# FDC9266_floppy_korr.net
KiCad netlist of a schematic drawn in EAGLE
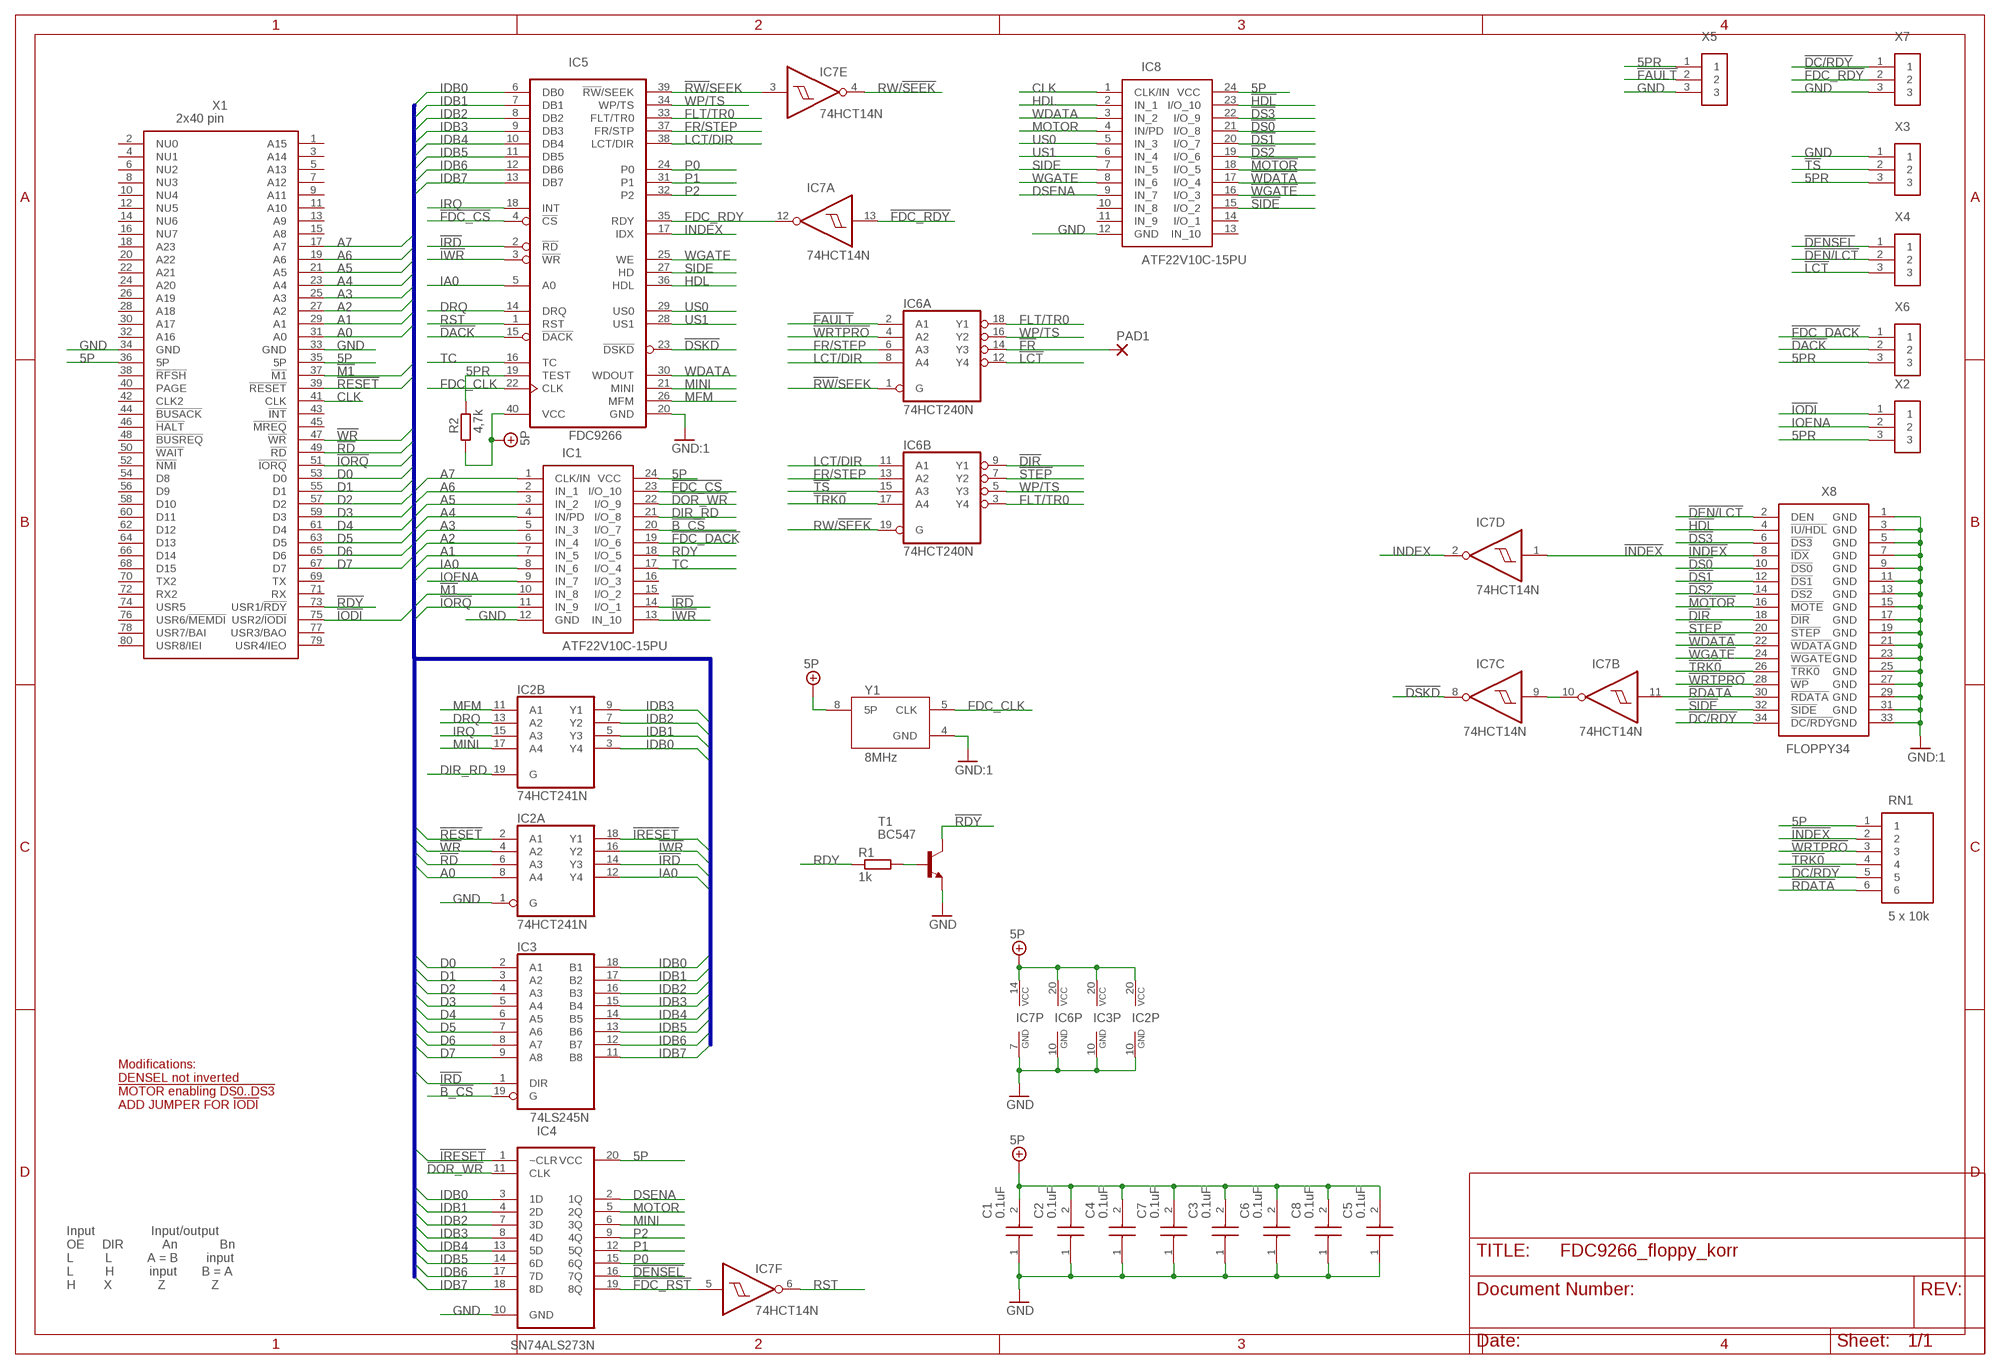
[diagram p0: schematic, sheet 1]

(export (version "E")
  (design (tool "Eeschema 10.0.6"))
  (components
    (comp (ref "C1")
      (value "0.1uF")
      (footprint "eagle-import:C315C103K5R5TA7303")
      (fields
        (field (name "ARROW_PART_NUMBER") "C315C103K5R5TA7303")
        (field (name "MOUSER_PART_NUMBER") "80-C315C103K5R-TR")
      )
      (libsource (lib "eagle-import") (part "C315C103K5R5TA7303"))
    )
    (comp (ref "C2")
      (value "0.1uF")
      (footprint "eagle-import:C315C103K5R5TA7303")
      (fields
        (field (name "ARROW_PART_NUMBER") "C315C103K5R5TA7303")
        (field (name "MOUSER_PART_NUMBER") "80-C315C103K5R-TR")
      )
      (libsource (lib "eagle-import") (part "C315C103K5R5TA7303"))
    )
    (comp (ref "C3")
      (value "0.1uF")
      (footprint "eagle-import:C315C103K5R5TA7303")
      (fields
        (field (name "ARROW_PART_NUMBER") "C315C103K5R5TA7303")
        (field (name "MOUSER_PART_NUMBER") "80-C315C103K5R-TR")
      )
      (libsource (lib "eagle-import") (part "C315C103K5R5TA7303"))
    )
    (comp (ref "C4")
      (value "0.1uF")
      (footprint "eagle-import:C315C103K5R5TA7303")
      (fields
        (field (name "ARROW_PART_NUMBER") "C315C103K5R5TA7303")
        (field (name "MOUSER_PART_NUMBER") "80-C315C103K5R-TR")
      )
      (libsource (lib "eagle-import") (part "C315C103K5R5TA7303"))
    )
    (comp (ref "C5")
      (value "0.1uF")
      (footprint "eagle-import:C315C103K5R5TA7303")
      (fields
        (field (name "ARROW_PART_NUMBER") "C315C103K5R5TA7303")
        (field (name "MOUSER_PART_NUMBER") "80-C315C103K5R-TR")
      )
      (libsource (lib "eagle-import") (part "C315C103K5R5TA7303"))
    )
    (comp (ref "C6")
      (value "0.1uF")
      (footprint "eagle-import:C315C103K5R5TA7303")
      (fields
        (field (name "ARROW_PART_NUMBER") "C315C103K5R5TA7303")
        (field (name "MOUSER_PART_NUMBER") "80-C315C103K5R-TR")
      )
      (libsource (lib "eagle-import") (part "C315C103K5R5TA7303"))
    )
    (comp (ref "C7")
      (value "0.1uF")
      (footprint "eagle-import:C315C103K5R5TA7303")
      (fields
        (field (name "ARROW_PART_NUMBER") "C315C103K5R5TA7303")
        (field (name "MOUSER_PART_NUMBER") "80-C315C103K5R-TR")
      )
      (libsource (lib "eagle-import") (part "C315C103K5R5TA7303"))
    )
    (comp (ref "C8")
      (value "0.1uF")
      (footprint "eagle-import:C315C103K5R5TA7303")
      (fields
        (field (name "ARROW_PART_NUMBER") "C315C103K5R5TA7303")
        (field (name "MOUSER_PART_NUMBER") "80-C315C103K5R-TR")
      )
      (libsource (lib "eagle-import") (part "C315C103K5R5TA7303"))
    )
    (comp (ref "IC1")
      (value "ATF22V10C-15PU")
      (footprint "eagle-import:DIP794W56P254L3188H533Q24N")
      (fields (field (name "MOUSER_PART_NUMBER") "556-AF22V10C15PU"))
      (libsource (lib "eagle-import") (part "ATF22V10C-15PU"))
    )
    (comp (ref "IC2")
      (value "74HCT241N")
      (footprint "eagle-import:DIL20")
      (libsource (lib "eagle-import") (part "74241NHCT"))
    )
    (comp (ref "IC3")
      (value "74LS245N")
      (footprint "eagle-import:DIL20")
      (libsource (lib "eagle-import") (part "74245NLS"))
    )
    (comp (ref "IC4")
      (value "SN74ALS273N")
      (footprint "eagle-import:DIP254P762X508-20")
      (libsource (lib "eagle-import") (part "SN74ALS273N"))
    )
    (comp (ref "IC5")
      (value "FDC9266")
      (footprint "eagle-import:DIP1550W53P254L5232H424Q40N")
      (libsource (lib "eagle-import") (part "FDC9266"))
    )
    (comp (ref "IC6")
      (value "74HCT240N")
      (footprint "eagle-import:DIL20")
      (libsource (lib "eagle-import") (part "74240NHCT"))
    )
    (comp (ref "IC7")
      (value "74HCT14N")
      (footprint "eagle-import:DIL14")
      (libsource (lib "eagle-import") (part "7414NHCT"))
    )
    (comp (ref "IC8")
      (value "ATF22V10C-15PU")
      (footprint "eagle-import:DIP794W56P254L3188H533Q24N")
      (fields (field (name "MOUSER_PART_NUMBER") "556-AF22V10C15PU"))
      (libsource (lib "eagle-import") (part "ATF22V10C-15PU"))
    )
    (comp (ref "PAD1")
      (value "WIREPAD1,6/0,8")
      (footprint "eagle-import:1,6_0,8")
      (libsource (lib "eagle-import") (part "WIREPAD1,6/0,8"))
    )
    (comp (ref "R1")
      (value "1k")
      (footprint "eagle-import:0207_10")
      (libsource (lib "eagle-import") (part "R_EU_020710"))
    )
    (comp (ref "R2")
      (value "4,7k")
      (footprint "eagle-import:0207_10")
      (libsource (lib "eagle-import") (part "R_EU_020710"))
    )
    (comp (ref "RN1")
      (value "5 x 10k")
      (footprint "eagle-import:4606X102103LF")
      (fields
        (field (name "ARROW_PART_NUMBER") "4606X-101-103LF")
        (field (name "MOUSER_PART_NUMBER") "652-4606X-1LF-10K")
      )
      (libsource (lib "eagle-import") (part "4606X-101-103LF"))
    )
    (comp (ref "T1")
      (value "BC547")
      (footprint "eagle-import:TO92")
      (libsource (lib "eagle-import") (part "BC547"))
    )
    (comp (ref "X1")
      (value "2x40 pin")
      (footprint "eagle-import:RC2014_80_RA")
      (libsource (lib "eagle-import") (part "RCBUS_80_RA"))
    )
    (comp (ref "X2")
      (value "TSW-103-07-G-S07")
      (footprint "eagle-import:TSW-103-XX-G-S")
      (fields (field (name "MF") "Samtec Inc.") (field (name "MPN") "TSW-103-07-G-S"))
      (libsource (lib "eagle-import") (part "TSW-103-07-G-S07"))
    )
    (comp (ref "X3")
      (value "TSW-103-07-G-S07")
      (footprint "eagle-import:TSW-103-XX-G-S")
      (fields (field (name "MF") "Samtec Inc.") (field (name "MPN") "TSW-103-07-G-S"))
      (libsource (lib "eagle-import") (part "TSW-103-07-G-S07"))
    )
    (comp (ref "X4")
      (value "TSW-103-07-G-S07")
      (footprint "eagle-import:TSW-103-XX-G-S")
      (fields (field (name "MF") "Samtec Inc.") (field (name "MPN") "TSW-103-07-G-S"))
      (libsource (lib "eagle-import") (part "TSW-103-07-G-S07"))
    )
    (comp (ref "X5")
      (value "TSW-103-07-G-S07")
      (footprint "eagle-import:TSW-103-XX-G-S")
      (fields (field (name "MF") "Samtec Inc.") (field (name "MPN") "TSW-103-07-G-S"))
      (libsource (lib "eagle-import") (part "TSW-103-07-G-S07"))
    )
    (comp (ref "X6")
      (value "TSW-103-07-G-S07")
      (footprint "eagle-import:TSW-103-XX-G-S")
      (fields (field (name "MF") "Samtec Inc.") (field (name "MPN") "TSW-103-07-G-S"))
      (libsource (lib "eagle-import") (part "TSW-103-07-G-S07"))
    )
    (comp (ref "X7")
      (value "TSW-103-07-G-S07")
      (footprint "eagle-import:TSW-103-XX-G-S")
      (fields (field (name "MF") "Samtec Inc.") (field (name "MPN") "TSW-103-07-G-S"))
      (libsource (lib "eagle-import") (part "TSW-103-07-G-S07"))
    )
    (comp (ref "X8")
      (value "FLOPPY34")
      (footprint "eagle-import:09185346323")
      (fields
        (field (name "ARROW_PART_NUMBER") "09185346323")
        (field (name "MOUSER_PART_NUMBER") "617-09-18-534-6323")
      )
      (libsource (lib "eagle-import") (part "FLOPPY34"))
    )
    (comp (ref "Y1")
      (value "8MHz")
      (footprint "eagle-import:ECS-2100AX-200")
      (fields
        (field (name "DIGIKEY_PART_NUMBER") "X964-ND")
        (field (name "MANUFACTURER") "ECS Inc.")
        (field (name "MPN") "ECS-2100AX-200")
        (field (name "CREATED_BY") "PCBLayout.com")
      )
      (libsource (lib "eagle-import") (part "ECS-2100AX-200"))
    )
  )
  (nets
    (net (code "1") (name "/5PR") (class "Default")
      (node (ref "IC5") (pin "19") (pinfunction "TEST_19") (pintype "input"))
      (node (ref "R2") (pin "2") (pinfunction "2_2") (pintype "passive"))
      (node (ref "X2") (pin "3") (pinfunction "3_3") (pintype "bidirectional"))
      (node (ref "X3") (pin "3") (pinfunction "3_3") (pintype "bidirectional"))
      (node (ref "X5") (pin "1") (pinfunction "1_1") (pintype "bidirectional"))
      (node (ref "X6") (pin "3") (pinfunction "3_3") (pintype "bidirectional"))
    )
    (net (code "2") (name "/A0") (class "Default")
      (node (ref "IC2") (pin "8") (pinfunction "A4_8") (pintype "input"))
      (node (ref "X1") (pin "31") (pinfunction "A0_31") (pintype "bidirectional"))
    )
    (net (code "3") (name "/A1") (class "Default")
      (node (ref "IC1") (pin "7") (pinfunction "IN_5_7") (pintype "bidirectional"))
      (node (ref "X1") (pin "29") (pinfunction "A1_29") (pintype "bidirectional"))
    )
    (net (code "4") (name "/A2") (class "Default")
      (node (ref "IC1") (pin "6") (pinfunction "IN_4_6") (pintype "bidirectional"))
      (node (ref "X1") (pin "27") (pinfunction "A2_27") (pintype "bidirectional"))
    )
    (net (code "5") (name "/A3") (class "Default")
      (node (ref "IC1") (pin "5") (pinfunction "IN_3_5") (pintype "bidirectional"))
      (node (ref "X1") (pin "25") (pinfunction "A3_25") (pintype "bidirectional"))
    )
    (net (code "6") (name "/A4") (class "Default")
      (node (ref "IC1") (pin "4") (pinfunction "IN/PD_4") (pintype "bidirectional"))
      (node (ref "X1") (pin "23") (pinfunction "A4_23") (pintype "bidirectional"))
    )
    (net (code "7") (name "/A5") (class "Default")
      (node (ref "IC1") (pin "3") (pinfunction "IN_2_3") (pintype "bidirectional"))
      (node (ref "X1") (pin "21") (pinfunction "A5_21") (pintype "bidirectional"))
    )
    (net (code "8") (name "/A6") (class "Default")
      (node (ref "IC1") (pin "2") (pinfunction "IN_1_2") (pintype "bidirectional"))
      (node (ref "X1") (pin "19") (pinfunction "A6_19") (pintype "bidirectional"))
    )
    (net (code "9") (name "/A7") (class "Default")
      (node (ref "IC1") (pin "1") (pinfunction "CLK/IN_1") (pintype "bidirectional"))
      (node (ref "X1") (pin "17") (pinfunction "A7_17") (pintype "bidirectional"))
    )
    (net (code "10") (name "/CLK") (class "Default")
      (node (ref "IC8") (pin "1") (pinfunction "CLK/IN_1") (pintype "bidirectional"))
      (node (ref "X1") (pin "41") (pinfunction "CLK_41") (pintype "bidirectional"))
    )
    (net (code "11") (name "/D0") (class "Default")
      (node (ref "IC3") (pin "2") (pinfunction "A1_2") (pintype "bidirectional"))
      (node (ref "X1") (pin "53") (pinfunction "D0_53") (pintype "bidirectional"))
    )
    (net (code "12") (name "/D1") (class "Default")
      (node (ref "IC3") (pin "3") (pinfunction "A2_3") (pintype "bidirectional"))
      (node (ref "X1") (pin "55") (pinfunction "D1_55") (pintype "bidirectional"))
    )
    (net (code "13") (name "/D2") (class "Default")
      (node (ref "IC3") (pin "4") (pinfunction "A3_4") (pintype "bidirectional"))
      (node (ref "X1") (pin "57") (pinfunction "D2_57") (pintype "bidirectional"))
    )
    (net (code "14") (name "/D3") (class "Default")
      (node (ref "IC3") (pin "5") (pinfunction "A4_5") (pintype "bidirectional"))
      (node (ref "X1") (pin "59") (pinfunction "D3_59") (pintype "bidirectional"))
    )
    (net (code "15") (name "/D4") (class "Default")
      (node (ref "IC3") (pin "6") (pinfunction "A5_6") (pintype "bidirectional"))
      (node (ref "X1") (pin "61") (pinfunction "D4_61") (pintype "bidirectional"))
    )
    (net (code "16") (name "/D5") (class "Default")
      (node (ref "IC3") (pin "7") (pinfunction "A6_7") (pintype "bidirectional"))
      (node (ref "X1") (pin "63") (pinfunction "D5_63") (pintype "bidirectional"))
    )
    (net (code "17") (name "/D6") (class "Default")
      (node (ref "IC3") (pin "8") (pinfunction "A7_8") (pintype "bidirectional"))
      (node (ref "X1") (pin "65") (pinfunction "D6_65") (pintype "bidirectional"))
    )
    (net (code "18") (name "/D7") (class "Default")
      (node (ref "IC3") (pin "9") (pinfunction "A8_9") (pintype "bidirectional"))
      (node (ref "X1") (pin "67") (pinfunction "D7_67") (pintype "bidirectional"))
    )
    (net (code "19") (name "/DIR_RD") (class "Default")
      (node (ref "IC1") (pin "21") (pinfunction "I/O_8_21") (pintype "bidirectional"))
      (node (ref "IC2") (pin "19") (pinfunction "G_19") (pintype "input"))
    )
    (net (code "20") (name "/DRQ") (class "Default")
      (node (ref "IC2") (pin "13") (pinfunction "A2_13") (pintype "input"))
      (node (ref "IC5") (pin "14") (pinfunction "DRQ_14") (pintype "output"))
    )
    (net (code "21") (name "/DSENA") (class "Default")
      (node (ref "IC4") (pin "2") (pinfunction "1Q_2") (pintype "output"))
      (node (ref "IC8") (pin "9") (pinfunction "IN_7_9") (pintype "bidirectional"))
    )
    (net (code "22") (name "/FDC_CLK") (class "Default")
      (node (ref "IC5") (pin "22") (pinfunction "CLK_22") (pintype "input"))
      (node (ref "Y1") (pin "5") (pinfunction "CLK_5") (pintype "output"))
    )
    (net (code "23") (name "/FDC_RDY") (class "Default")
      (node (ref "IC5") (pin "35") (pinfunction "RDY_35") (pintype "input"))
      (node (ref "IC7") (pin "12") (pinfunction "O_12") (pintype "output"))
    )
    (net (code "24") (name "/FLT{slash}TR0") (class "Default")
      (node (ref "IC5") (pin "33") (pinfunction "FLT/TR0_33") (pintype "input"))
      (node (ref "IC6") (pin "18") (pinfunction "Y1_18") (pintype "tri_state"))
      (node (ref "IC6") (pin "3") (pinfunction "Y4_3") (pintype "tri_state"))
    )
    (net (code "25") (name "/FR{slash}STEP") (class "Default")
      (node (ref "IC5") (pin "37") (pinfunction "FR/STP_37") (pintype "output"))
      (node (ref "IC6") (pin "13") (pinfunction "A2_13") (pintype "input"))
      (node (ref "IC6") (pin "6") (pinfunction "A3_6") (pintype "input"))
    )
    (net (code "26") (name "/HDL") (class "Default")
      (node (ref "IC5") (pin "36") (pinfunction "HDL_36") (pintype "output"))
      (node (ref "IC8") (pin "2") (pinfunction "IN_1_2") (pintype "bidirectional"))
    )
    (net (code "27") (name "/IA0") (class "Default")
      (node (ref "IC1") (pin "8") (pinfunction "IN_6_8") (pintype "bidirectional"))
      (node (ref "IC2") (pin "12") (pinfunction "Y4_12") (pintype "tri_state"))
      (node (ref "IC5") (pin "5") (pinfunction "A0_5") (pintype "input"))
    )
    (net (code "28") (name "/IDB0") (class "Default")
      (node (ref "IC2") (pin "3") (pinfunction "Y4_3") (pintype "tri_state"))
      (node (ref "IC3") (pin "18") (pinfunction "B1_18") (pintype "bidirectional"))
      (node (ref "IC4") (pin "3") (pinfunction "1D_3") (pintype "input"))
      (node (ref "IC5") (pin "6") (pinfunction "DB0_6") (pintype "bidirectional"))
    )
    (net (code "29") (name "/IDB1") (class "Default")
      (node (ref "IC2") (pin "5") (pinfunction "Y3_5") (pintype "tri_state"))
      (node (ref "IC3") (pin "17") (pinfunction "B2_17") (pintype "bidirectional"))
      (node (ref "IC4") (pin "4") (pinfunction "2D_4") (pintype "input"))
      (node (ref "IC5") (pin "7") (pinfunction "DB1_7") (pintype "bidirectional"))
    )
    (net (code "30") (name "/IDB2") (class "Default")
      (node (ref "IC2") (pin "7") (pinfunction "Y2_7") (pintype "tri_state"))
      (node (ref "IC3") (pin "16") (pinfunction "B3_16") (pintype "bidirectional"))
      (node (ref "IC4") (pin "7") (pinfunction "3D_7") (pintype "input"))
      (node (ref "IC5") (pin "8") (pinfunction "DB2_8") (pintype "bidirectional"))
    )
    (net (code "31") (name "/IDB3") (class "Default")
      (node (ref "IC2") (pin "9") (pinfunction "Y1_9") (pintype "tri_state"))
      (node (ref "IC3") (pin "15") (pinfunction "B4_15") (pintype "bidirectional"))
      (node (ref "IC4") (pin "8") (pinfunction "4D_8") (pintype "input"))
      (node (ref "IC5") (pin "9") (pinfunction "DB3_9") (pintype "bidirectional"))
    )
    (net (code "32") (name "/IDB4") (class "Default")
      (node (ref "IC3") (pin "14") (pinfunction "B5_14") (pintype "bidirectional"))
      (node (ref "IC4") (pin "13") (pinfunction "5D_13") (pintype "input"))
      (node (ref "IC5") (pin "10") (pinfunction "DB4_10") (pintype "bidirectional"))
    )
    (net (code "33") (name "/IDB5") (class "Default")
      (node (ref "IC3") (pin "13") (pinfunction "B6_13") (pintype "bidirectional"))
      (node (ref "IC4") (pin "14") (pinfunction "6D_14") (pintype "input"))
      (node (ref "IC5") (pin "11") (pinfunction "DB5_11") (pintype "bidirectional"))
    )
    (net (code "34") (name "/IDB6") (class "Default")
      (node (ref "IC3") (pin "12") (pinfunction "B7_12") (pintype "bidirectional"))
      (node (ref "IC4") (pin "17") (pinfunction "7D_17") (pintype "input"))
      (node (ref "IC5") (pin "12") (pinfunction "DB6_12") (pintype "bidirectional"))
    )
    (net (code "35") (name "/IDB7") (class "Default")
      (node (ref "IC3") (pin "11") (pinfunction "B8_11") (pintype "bidirectional"))
      (node (ref "IC4") (pin "18") (pinfunction "8D_18") (pintype "input"))
      (node (ref "IC5") (pin "13") (pinfunction "DB7_13") (pintype "bidirectional"))
    )
    (net (code "36") (name "/INDEX") (class "Default")
      (node (ref "IC5") (pin "17") (pinfunction "IDX_17") (pintype "input"))
      (node (ref "IC7") (pin "2") (pinfunction "O_2") (pintype "output"))
    )
    (net (code "37") (name "/IOENA") (class "Default")
      (node (ref "IC1") (pin "9") (pinfunction "IN_7_9") (pintype "bidirectional"))
      (node (ref "X2") (pin "2") (pinfunction "2_2") (pintype "bidirectional"))
    )
    (net (code "38") (name "/IRQ") (class "Default")
      (node (ref "IC2") (pin "15") (pinfunction "A3_15") (pintype "input"))
      (node (ref "IC5") (pin "18") (pinfunction "INT_18") (pintype "output"))
    )
    (net (code "39") (name "/LCT{slash}DIR") (class "Default")
      (node (ref "IC5") (pin "38") (pinfunction "LCT/DIR_38") (pintype "output"))
      (node (ref "IC6") (pin "11") (pinfunction "A1_11") (pintype "input"))
      (node (ref "IC6") (pin "8") (pinfunction "A4_8") (pintype "input"))
    )
    (net (code "40") (name "/MFM") (class "Default")
      (node (ref "IC2") (pin "11") (pinfunction "A1_11") (pintype "input"))
      (node (ref "IC5") (pin "26") (pinfunction "MFM_26") (pintype "output"))
    )
    (net (code "41") (name "/MINI") (class "Default")
      (node (ref "IC2") (pin "17") (pinfunction "A4_17") (pintype "input"))
      (node (ref "IC4") (pin "6") (pinfunction "3Q_6") (pintype "output"))
      (node (ref "IC5") (pin "21") (pinfunction "MINI_21") (pintype "input"))
    )
    (net (code "42") (name "/MOTOR") (class "Default")
      (node (ref "IC4") (pin "5") (pinfunction "2Q_5") (pintype "output"))
      (node (ref "IC8") (pin "4") (pinfunction "IN/PD_4") (pintype "bidirectional"))
    )
    (net (code "43") (name "/P0") (class "Default")
      (node (ref "IC4") (pin "15") (pinfunction "6Q_15") (pintype "output"))
      (node (ref "IC5") (pin "24") (pinfunction "P0_24") (pintype "input"))
    )
    (net (code "44") (name "/P1") (class "Default")
      (node (ref "IC4") (pin "12") (pinfunction "5Q_12") (pintype "output"))
      (node (ref "IC5") (pin "31") (pinfunction "P1_31") (pintype "input"))
    )
    (net (code "45") (name "/P2") (class "Default")
      (node (ref "IC4") (pin "9") (pinfunction "4Q_9") (pintype "output"))
      (node (ref "IC5") (pin "32") (pinfunction "P2_32") (pintype "input"))
    )
    (net (code "46") (name "/RDY") (class "Default")
      (node (ref "IC1") (pin "18") (pinfunction "I/O_5_18") (pintype "bidirectional"))
      (node (ref "R1") (pin "1") (pinfunction "1_1") (pintype "passive"))
    )
    (net (code "47") (name "/RST") (class "Default")
      (node (ref "IC5") (pin "1") (pinfunction "RST_1") (pintype "input"))
      (node (ref "IC7") (pin "6") (pinfunction "O_6") (pintype "output"))
    )
    (net (code "48") (name "/RW{slash}~{SEEK}") (class "Default")
      (node (ref "IC6") (pin "19") (pinfunction "G_19") (pintype "input"))
      (node (ref "IC7") (pin "4") (pinfunction "O_4") (pintype "output"))
    )
    (net (code "49") (name "/SIDE") (class "Default")
      (node (ref "IC5") (pin "27") (pinfunction "HD_27") (pintype "output"))
      (node (ref "IC8") (pin "7") (pinfunction "IN_5_7") (pintype "bidirectional"))
    )
    (net (code "50") (name "/TC") (class "Default")
      (node (ref "IC1") (pin "17") (pinfunction "I/O_4_17") (pintype "bidirectional"))
      (node (ref "IC5") (pin "16") (pinfunction "TC_16") (pintype "input"))
    )
    (net (code "51") (name "/US0") (class "Default")
      (node (ref "IC5") (pin "29") (pinfunction "US0_29") (pintype "output"))
      (node (ref "IC8") (pin "5") (pinfunction "IN_3_5") (pintype "bidirectional"))
    )
    (net (code "52") (name "/US1") (class "Default")
      (node (ref "IC5") (pin "28") (pinfunction "US1_28") (pintype "output"))
      (node (ref "IC8") (pin "6") (pinfunction "IN_4_6") (pintype "bidirectional"))
    )
    (net (code "53") (name "/WDATA") (class "Default")
      (node (ref "IC5") (pin "30") (pinfunction "WDOUT_30") (pintype "output"))
      (node (ref "IC8") (pin "3") (pinfunction "IN_2_3") (pintype "bidirectional"))
    )
    (net (code "54") (name "/WGATE") (class "Default")
      (node (ref "IC5") (pin "25") (pinfunction "WE_25") (pintype "output"))
      (node (ref "IC8") (pin "8") (pinfunction "IN_6_8") (pintype "bidirectional"))
    )
    (net (code "55") (name "/WP{slash}TS") (class "Default")
      (node (ref "IC5") (pin "34") (pinfunction "WP/TS_34") (pintype "input"))
      (node (ref "IC6") (pin "16") (pinfunction "Y2_16") (pintype "tri_state"))
      (node (ref "IC6") (pin "5") (pinfunction "Y3_5") (pintype "tri_state"))
    )
    (net (code "56") (name "/~{B_CS}") (class "Default")
      (node (ref "IC1") (pin "20") (pinfunction "I/O_7_20") (pintype "bidirectional"))
      (node (ref "IC3") (pin "19") (pinfunction "G_19") (pintype "input"))
    )
    (net (code "57") (name "/~{DACK}") (class "Default")
      (node (ref "IC5") (pin "15") (pinfunction "~{DACK}_15") (pintype "input"))
      (node (ref "X6") (pin "2") (pinfunction "2_2") (pintype "bidirectional"))
    )
    (net (code "58") (name "/~{DC{slash}RDY}") (class "Default")
      (node (ref "RN1") (pin "5") (pinfunction "5_5") (pintype "bidirectional"))
      (node (ref "X7") (pin "1") (pinfunction "1_1") (pintype "bidirectional"))
      (node (ref "X8") (pin "34") (pinfunction "~{DC/RDY}_34") (pintype "output"))
    )
    (net (code "59") (name "/~{DENSEL}") (class "Default")
      (node (ref "IC4") (pin "16") (pinfunction "7Q_16") (pintype "output"))
      (node (ref "X4") (pin "1") (pinfunction "1_1") (pintype "bidirectional"))
    )
    (net (code "60") (name "/~{DEN{slash}LCT}") (class "Default")
      (node (ref "X4") (pin "2") (pinfunction "2_2") (pintype "bidirectional"))
      (node (ref "X8") (pin "2") (pinfunction "DEN_2") (pintype "input"))
    )
    (net (code "61") (name "/~{DIR}") (class "Default")
      (node (ref "IC6") (pin "9") (pinfunction "Y1_9") (pintype "tri_state"))
      (node (ref "X8") (pin "18") (pinfunction "~{DIR}_18") (pintype "input"))
    )
    (net (code "62") (name "/~{DOR_WR}") (class "Default")
      (node (ref "IC1") (pin "22") (pinfunction "I/O_9_22") (pintype "bidirectional"))
      (node (ref "IC4") (pin "11") (pinfunction "CLK_11") (pintype "input"))
    )
    (net (code "63") (name "/~{DS0}") (class "Default")
      (node (ref "IC8") (pin "21") (pinfunction "I/O_8_21") (pintype "bidirectional"))
      (node (ref "X8") (pin "10") (pinfunction "~{DS0}_10") (pintype "input"))
    )
    (net (code "64") (name "/~{DS1}") (class "Default")
      (node (ref "IC8") (pin "20") (pinfunction "I/O_7_20") (pintype "bidirectional"))
      (node (ref "X8") (pin "12") (pinfunction "~{DS1}_12") (pintype "input"))
    )
    (net (code "65") (name "/~{DS2}") (class "Default")
      (node (ref "IC8") (pin "19") (pinfunction "I/O_6_19") (pintype "bidirectional"))
      (node (ref "X8") (pin "14") (pinfunction "~{DS2}_14") (pintype "input"))
    )
    (net (code "66") (name "/~{DS3}") (class "Default")
      (node (ref "IC8") (pin "22") (pinfunction "I/O_9_22") (pintype "bidirectional"))
      (node (ref "X8") (pin "6") (pinfunction "~{DS3}_6") (pintype "input"))
    )
    (net (code "67") (name "/~{DSKD}") (class "Default")
      (node (ref "IC5") (pin "23") (pinfunction "~{DSKD}_23") (pintype "input"))
      (node (ref "IC7") (pin "8") (pinfunction "O_8") (pintype "output"))
    )
    (net (code "68") (name "/~{FAULT}") (class "Default")
      (node (ref "IC6") (pin "2") (pinfunction "A1_2") (pintype "input"))
      (node (ref "X5") (pin "2") (pinfunction "2_2") (pintype "bidirectional"))
    )
    (net (code "69") (name "/~{FDC_CS}") (class "Default")
      (node (ref "IC1") (pin "23") (pinfunction "I/O_10_23") (pintype "bidirectional"))
      (node (ref "IC5") (pin "4") (pinfunction "~{CS}_4") (pintype "input"))
    )
    (net (code "70") (name "/~{FDC_DACK}") (class "Default")
      (node (ref "IC1") (pin "19") (pinfunction "I/O_6_19") (pintype "bidirectional"))
      (node (ref "X6") (pin "1") (pinfunction "1_1") (pintype "bidirectional"))
    )
    (net (code "71") (name "/~{FDC_RDY}") (class "Default")
      (node (ref "IC7") (pin "13") (pinfunction "I_13") (pintype "input"))
      (node (ref "X7") (pin "2") (pinfunction "2_2") (pintype "bidirectional"))
    )
    (net (code "72") (name "/~{FDC_RST}") (class "Default")
      (node (ref "IC4") (pin "19") (pinfunction "8Q_19") (pintype "output"))
      (node (ref "IC7") (pin "5") (pinfunction "I_5") (pintype "input"))
    )
    (net (code "73") (name "/~{FR}") (class "Default")
      (node (ref "IC6") (pin "14") (pinfunction "Y3_14") (pintype "tri_state"))
      (node (ref "PAD1") (pin "1") (pinfunction "P_1") (pintype "passive"))
    )
    (net (code "74") (name "/~{HDL}") (class "Default")
      (node (ref "IC8") (pin "23") (pinfunction "I/O_10_23") (pintype "bidirectional"))
      (node (ref "X8") (pin "4") (pinfunction "~{IU/HDL}_4") (pintype "input"))
    )
    (net (code "75") (name "/~{INDEX}") (class "Default")
      (node (ref "IC7") (pin "1") (pinfunction "I_1") (pintype "input"))
      (node (ref "RN1") (pin "2") (pinfunction "2_2") (pintype "bidirectional"))
      (node (ref "X8") (pin "8") (pinfunction "~{IDX}_8") (pintype "output"))
    )
    (net (code "76") (name "/~{IODI}") (class "Default")
      (node (ref "X1") (pin "75") (pinfunction "USR2/~{IODI}_75") (pintype "bidirectional"))
      (node (ref "X2") (pin "1") (pinfunction "1_1") (pintype "bidirectional"))
    )
    (net (code "77") (name "/~{IORQ}") (class "Default")
      (node (ref "IC1") (pin "11") (pinfunction "IN_9_11") (pintype "bidirectional"))
      (node (ref "X1") (pin "51") (pinfunction "~{IORQ}_51") (pintype "bidirectional"))
    )
    (net (code "78") (name "/~{IRD}") (class "Default")
      (node (ref "IC1") (pin "14") (pinfunction "I/O_1_14") (pintype "bidirectional"))
      (node (ref "IC2") (pin "14") (pinfunction "Y3_14") (pintype "tri_state"))
      (node (ref "IC3") (pin "1") (pinfunction "DIR_1") (pintype "input"))
      (node (ref "IC5") (pin "2") (pinfunction "~{RD}_2") (pintype "input"))
    )
    (net (code "79") (name "/~{IRESET}") (class "Default")
      (node (ref "IC2") (pin "18") (pinfunction "Y1_18") (pintype "tri_state"))
      (node (ref "IC4") (pin "1") (pinfunction "~{CLR}_1") (pintype "input"))
    )
    (net (code "80") (name "/~{IWR}") (class "Default")
      (node (ref "IC1") (pin "13") (pinfunction "IN_10_13") (pintype "bidirectional"))
      (node (ref "IC2") (pin "16") (pinfunction "Y2_16") (pintype "tri_state"))
      (node (ref "IC5") (pin "3") (pinfunction "~{WR}_3") (pintype "input"))
    )
    (net (code "81") (name "/~{LCT}") (class "Default")
      (node (ref "IC6") (pin "12") (pinfunction "Y4_12") (pintype "tri_state"))
      (node (ref "X4") (pin "3") (pinfunction "3_3") (pintype "bidirectional"))
    )
    (net (code "82") (name "/~{M1}") (class "Default")
      (node (ref "IC1") (pin "10") (pinfunction "IN_8_10") (pintype "bidirectional"))
      (node (ref "X1") (pin "37") (pinfunction "~{M1}_37") (pintype "bidirectional"))
    )
    (net (code "83") (name "/~{MOTOR}") (class "Default")
      (node (ref "IC8") (pin "18") (pinfunction "I/O_5_18") (pintype "bidirectional"))
      (node (ref "X8") (pin "16") (pinfunction "~{MOTE}_16") (pintype "input"))
    )
    (net (code "84") (name "/~{RDATA}") (class "Default")
      (node (ref "IC7") (pin "11") (pinfunction "I_11") (pintype "input"))
      (node (ref "RN1") (pin "6") (pinfunction "6_6") (pintype "bidirectional"))
      (node (ref "X8") (pin "30") (pinfunction "~{RDATA}_30") (pintype "output"))
    )
    (net (code "85") (name "/~{RDY}") (class "Default")
      (node (ref "T1") (pin "3") (pinfunction "C_3") (pintype "passive"))
      (node (ref "X1") (pin "73") (pinfunction "USR1/~{RDY}_73") (pintype "bidirectional"))
    )
    (net (code "86") (name "/~{RD}") (class "Default")
      (node (ref "IC2") (pin "6") (pinfunction "A3_6") (pintype "input"))
      (node (ref "X1") (pin "49") (pinfunction "~{RD}_49") (pintype "bidirectional"))
    )
    (net (code "87") (name "/~{RESET}") (class "Default")
      (node (ref "IC2") (pin "2") (pinfunction "A1_2") (pintype "input"))
      (node (ref "X1") (pin "39") (pinfunction "~{RESET}_39") (pintype "bidirectional"))
    )
    (net (code "88") (name "/~{RW{slash}}SEEK") (class "Default")
      (node (ref "IC5") (pin "39") (pinfunction "~{RW}/SEEK_39") (pintype "output"))
      (node (ref "IC6") (pin "1") (pinfunction "G_1") (pintype "input"))
      (node (ref "IC7") (pin "3") (pinfunction "I_3") (pintype "input"))
    )
    (net (code "89") (name "/~{SIDE}") (class "Default")
      (node (ref "IC8") (pin "15") (pinfunction "I/O_2_15") (pintype "bidirectional"))
      (node (ref "X8") (pin "32") (pinfunction "~{SIDE}_32") (pintype "input"))
    )
    (net (code "90") (name "/~{STEP}") (class "Default")
      (node (ref "IC6") (pin "7") (pinfunction "Y2_7") (pintype "tri_state"))
      (node (ref "X8") (pin "20") (pinfunction "~{STEP}_20") (pintype "input"))
    )
    (net (code "91") (name "/~{TRK0}") (class "Default")
      (node (ref "IC6") (pin "17") (pinfunction "A4_17") (pintype "input"))
      (node (ref "RN1") (pin "4") (pinfunction "4_4") (pintype "bidirectional"))
      (node (ref "X8") (pin "26") (pinfunction "~{TRK0}_26") (pintype "output"))
    )
    (net (code "92") (name "/~{TS}") (class "Default")
      (node (ref "IC6") (pin "15") (pinfunction "A3_15") (pintype "input"))
      (node (ref "X3") (pin "2") (pinfunction "2_2") (pintype "bidirectional"))
    )
    (net (code "93") (name "/~{WDATA}") (class "Default")
      (node (ref "IC8") (pin "17") (pinfunction "I/O_4_17") (pintype "bidirectional"))
      (node (ref "X8") (pin "22") (pinfunction "~{WDATA}_22") (pintype "input"))
    )
    (net (code "94") (name "/~{WGATE}") (class "Default")
      (node (ref "IC8") (pin "16") (pinfunction "I/O_3_16") (pintype "bidirectional"))
      (node (ref "X8") (pin "24") (pinfunction "~{WGATE}_24") (pintype "input"))
    )
    (net (code "95") (name "/~{WRTPRO}") (class "Default")
      (node (ref "IC6") (pin "4") (pinfunction "A2_4") (pintype "input"))
      (node (ref "RN1") (pin "3") (pinfunction "3_3") (pintype "bidirectional"))
      (node (ref "X8") (pin "28") (pinfunction "~{WP}_28") (pintype "output"))
    )
    (net (code "96") (name "/~{WR}") (class "Default")
      (node (ref "IC2") (pin "4") (pinfunction "A2_4") (pintype "input"))
      (node (ref "X1") (pin "47") (pinfunction "~{WR}_47") (pintype "bidirectional"))
    )
    (net (code "97") (name "5P") (class "Default")
      (node (ref "C1") (pin "2") (pinfunction "2_2") (pintype "bidirectional"))
      (node (ref "C2") (pin "2") (pinfunction "2_2") (pintype "bidirectional"))
      (node (ref "C3") (pin "2") (pinfunction "2_2") (pintype "bidirectional"))
      (node (ref "C4") (pin "2") (pinfunction "2_2") (pintype "bidirectional"))
      (node (ref "C5") (pin "2") (pinfunction "2_2") (pintype "bidirectional"))
      (node (ref "C6") (pin "2") (pinfunction "2_2") (pintype "bidirectional"))
      (node (ref "C7") (pin "2") (pinfunction "2_2") (pintype "bidirectional"))
      (node (ref "C8") (pin "2") (pinfunction "2_2") (pintype "bidirectional"))
      (node (ref "IC1") (pin "24") (pinfunction "VCC_24") (pintype "bidirectional"))
      (node (ref "IC2") (pin "20") (pinfunction "VCC_20") (pintype "power_in"))
      (node (ref "IC3") (pin "20") (pinfunction "VCC_20") (pintype "power_in"))
      (node (ref "IC4") (pin "20") (pinfunction "VCC_20") (pintype "power_in"))
      (node (ref "IC5") (pin "40") (pinfunction "VCC_40") (pintype "power_in"))
      (node (ref "IC6") (pin "20") (pinfunction "VCC_20") (pintype "power_in"))
      (node (ref "IC7") (pin "14") (pinfunction "VCC_14") (pintype "power_in"))
      (node (ref "IC8") (pin "24") (pinfunction "VCC_24") (pintype "bidirectional"))
      (node (ref "R2") (pin "1") (pinfunction "1_1") (pintype "passive"))
      (node (ref "RN1") (pin "1") (pinfunction "1_1") (pintype "bidirectional"))
      (node (ref "X1") (pin "35") (pinfunction "5P_35") (pintype "power_in"))
      (node (ref "X1") (pin "36") (pinfunction "5P_36") (pintype "power_in"))
      (node (ref "Y1") (pin "8") (pinfunction "5P_8") (pintype "power_in"))
    )
    (net (code "98") (name "GND") (class "Default")
      (node (ref "C1") (pin "1") (pinfunction "1_1") (pintype "bidirectional"))
      (node (ref "C2") (pin "1") (pinfunction "1_1") (pintype "bidirectional"))
      (node (ref "C3") (pin "1") (pinfunction "1_1") (pintype "bidirectional"))
      (node (ref "C4") (pin "1") (pinfunction "1_1") (pintype "bidirectional"))
      (node (ref "C5") (pin "1") (pinfunction "1_1") (pintype "bidirectional"))
      (node (ref "C6") (pin "1") (pinfunction "1_1") (pintype "bidirectional"))
      (node (ref "C7") (pin "1") (pinfunction "1_1") (pintype "bidirectional"))
      (node (ref "C8") (pin "1") (pinfunction "1_1") (pintype "bidirectional"))
      (node (ref "IC1") (pin "12") (pinfunction "GND_12") (pintype "bidirectional"))
      (node (ref "IC2") (pin "1") (pinfunction "G_1") (pintype "input"))
      (node (ref "IC2") (pin "10") (pinfunction "GND_10") (pintype "power_in"))
      (node (ref "IC3") (pin "10") (pinfunction "GND_10") (pintype "power_in"))
      (node (ref "IC4") (pin "10") (pinfunction "GND_10") (pintype "power_in"))
      (node (ref "IC5") (pin "20") (pinfunction "GND_20") (pintype "power_in"))
      (node (ref "IC6") (pin "10") (pinfunction "GND_10") (pintype "power_in"))
      (node (ref "IC7") (pin "7") (pinfunction "GND_7") (pintype "power_in"))
      (node (ref "IC8") (pin "12") (pinfunction "GND_12") (pintype "bidirectional"))
      (node (ref "T1") (pin "1") (pinfunction "E_1") (pintype "passive"))
      (node (ref "X1") (pin "33") (pinfunction "GND_33") (pintype "power_in"))
      (node (ref "X1") (pin "34") (pinfunction "GND_34") (pintype "power_in"))
      (node (ref "X3") (pin "1") (pinfunction "1_1") (pintype "bidirectional"))
      (node (ref "X5") (pin "3") (pinfunction "3_3") (pintype "bidirectional"))
      (node (ref "X7") (pin "3") (pinfunction "3_3") (pintype "bidirectional"))
      (node (ref "X8") (pin "1") (pinfunction "GND_1") (pintype "power_in"))
      (node (ref "X8") (pin "11") (pinfunction "GND_11") (pintype "power_in"))
      (node (ref "X8") (pin "13") (pinfunction "GND_13") (pintype "power_in"))
      (node (ref "X8") (pin "15") (pinfunction "GND_15") (pintype "power_in"))
      (node (ref "X8") (pin "17") (pinfunction "GND_17") (pintype "power_in"))
      (node (ref "X8") (pin "19") (pinfunction "GND_19") (pintype "power_in"))
      (node (ref "X8") (pin "21") (pinfunction "GND_21") (pintype "power_in"))
      (node (ref "X8") (pin "23") (pinfunction "GND_23") (pintype "power_in"))
      (node (ref "X8") (pin "25") (pinfunction "GND_25") (pintype "power_in"))
      (node (ref "X8") (pin "27") (pinfunction "GND_27") (pintype "power_in"))
      (node (ref "X8") (pin "29") (pinfunction "GND_29") (pintype "power_in"))
      (node (ref "X8") (pin "3") (pinfunction "GND_3") (pintype "power_in"))
      (node (ref "X8") (pin "31") (pinfunction "GND_31") (pintype "power_in"))
      (node (ref "X8") (pin "33") (pinfunction "GND_33") (pintype "power_in"))
      (node (ref "X8") (pin "5") (pinfunction "GND_5") (pintype "power_in"))
      (node (ref "X8") (pin "7") (pinfunction "GND_7") (pintype "power_in"))
      (node (ref "X8") (pin "9") (pinfunction "GND_9") (pintype "power_in"))
      (node (ref "Y1") (pin "4") (pinfunction "GND_4") (pintype "power_in"))
    )
    (net (code "99") (name "Net-(IC7B-O)") (class "Default")
      (node (ref "IC7") (pin "10") (pinfunction "O_10") (pintype "output"))
      (node (ref "IC7") (pin "9") (pinfunction "I_9") (pintype "input"))
    )
    (net (code "100") (name "Net-(T1-B)") (class "Default")
      (node (ref "R1") (pin "2") (pinfunction "2_2") (pintype "passive"))
      (node (ref "T1") (pin "2") (pinfunction "B_2") (pintype "passive"))
    )
    (net (code "101") (name "unconnected-(IC1-I{slash}O_2-Pad15)") (class "Default")
      (node (ref "IC1") (pin "15") (pinfunction "I/O_2_15") (pintype "bidirectional"))
    )
    (net (code "102") (name "unconnected-(IC1-I{slash}O_3-Pad16)") (class "Default")
      (node (ref "IC1") (pin "16") (pinfunction "I/O_3_16") (pintype "bidirectional"))
    )
    (net (code "103") (name "unconnected-(IC8-IN_8-Pad10)") (class "Default")
      (node (ref "IC8") (pin "10") (pinfunction "IN_8_10") (pintype "bidirectional"))
    )
    (net (code "104") (name "unconnected-(IC8-IN_9-Pad11)") (class "Default")
      (node (ref "IC8") (pin "11") (pinfunction "IN_9_11") (pintype "bidirectional"))
    )
    (net (code "105") (name "unconnected-(IC8-IN_10-Pad13)") (class "Default")
      (node (ref "IC8") (pin "13") (pinfunction "IN_10_13") (pintype "bidirectional"))
    )
    (net (code "106") (name "unconnected-(IC8-I{slash}O_1-Pad14)") (class "Default")
      (node (ref "IC8") (pin "14") (pinfunction "I/O_1_14") (pintype "bidirectional"))
    )
    (net (code "107") (name "unconnected-(X1-A8-Pad15)") (class "Default")
      (node (ref "X1") (pin "15") (pinfunction "A8_15") (pintype "bidirectional"))
    )
    (net (code "108") (name "unconnected-(X1-A9-Pad13)") (class "Default")
      (node (ref "X1") (pin "13") (pinfunction "A9_13") (pintype "bidirectional"))
    )
    (net (code "109") (name "unconnected-(X1-A10-Pad11)") (class "Default")
      (node (ref "X1") (pin "11") (pinfunction "A10_11") (pintype "bidirectional"))
    )
    (net (code "110") (name "unconnected-(X1-A11-Pad9)") (class "Default")
      (node (ref "X1") (pin "9") (pinfunction "A11_9") (pintype "bidirectional"))
    )
    (net (code "111") (name "unconnected-(X1-A12-Pad7)") (class "Default")
      (node (ref "X1") (pin "7") (pinfunction "A12_7") (pintype "bidirectional"))
    )
    (net (code "112") (name "unconnected-(X1-A13-Pad5)") (class "Default")
      (node (ref "X1") (pin "5") (pinfunction "A13_5") (pintype "bidirectional"))
    )
    (net (code "113") (name "unconnected-(X1-A14-Pad3)") (class "Default")
      (node (ref "X1") (pin "3") (pinfunction "A14_3") (pintype "bidirectional"))
    )
    (net (code "114") (name "unconnected-(X1-A15-Pad1)") (class "Default")
      (node (ref "X1") (pin "1") (pinfunction "A15_1") (pintype "bidirectional"))
    )
    (net (code "115") (name "unconnected-(X1-A16-Pad32)") (class "Default")
      (node (ref "X1") (pin "32") (pinfunction "A16_32") (pintype "bidirectional"))
    )
    (net (code "116") (name "unconnected-(X1-A17-Pad30)") (class "Default")
      (node (ref "X1") (pin "30") (pinfunction "A17_30") (pintype "bidirectional"))
    )
    (net (code "117") (name "unconnected-(X1-A18-Pad28)") (class "Default")
      (node (ref "X1") (pin "28") (pinfunction "A18_28") (pintype "bidirectional"))
    )
    (net (code "118") (name "unconnected-(X1-A19-Pad26)") (class "Default")
      (node (ref "X1") (pin "26") (pinfunction "A19_26") (pintype "bidirectional"))
    )
    (net (code "119") (name "unconnected-(X1-A20-Pad24)") (class "Default")
      (node (ref "X1") (pin "24") (pinfunction "A20_24") (pintype "bidirectional"))
    )
    (net (code "120") (name "unconnected-(X1-A21-Pad22)") (class "Default")
      (node (ref "X1") (pin "22") (pinfunction "A21_22") (pintype "bidirectional"))
    )
    (net (code "121") (name "unconnected-(X1-A22-Pad20)") (class "Default")
      (node (ref "X1") (pin "20") (pinfunction "A22_20") (pintype "bidirectional"))
    )
    (net (code "122") (name "unconnected-(X1-A23-Pad18)") (class "Default")
      (node (ref "X1") (pin "18") (pinfunction "A23_18") (pintype "bidirectional"))
    )
    (net (code "123") (name "unconnected-(X1-CLK2-Pad42)") (class "Default")
      (node (ref "X1") (pin "42") (pinfunction "CLK2_42") (pintype "bidirectional"))
    )
    (net (code "124") (name "unconnected-(X1-D8-Pad54)") (class "Default")
      (node (ref "X1") (pin "54") (pinfunction "D8_54") (pintype "bidirectional"))
    )
    (net (code "125") (name "unconnected-(X1-D9-Pad56)") (class "Default")
      (node (ref "X1") (pin "56") (pinfunction "D9_56") (pintype "bidirectional"))
    )
    (net (code "126") (name "unconnected-(X1-D10-Pad58)") (class "Default")
      (node (ref "X1") (pin "58") (pinfunction "D10_58") (pintype "bidirectional"))
    )
    (net (code "127") (name "unconnected-(X1-D11-Pad60)") (class "Default")
      (node (ref "X1") (pin "60") (pinfunction "D11_60") (pintype "bidirectional"))
    )
    (net (code "128") (name "unconnected-(X1-D12-Pad62)") (class "Default")
      (node (ref "X1") (pin "62") (pinfunction "D12_62") (pintype "bidirectional"))
    )
    (net (code "129") (name "unconnected-(X1-D13-Pad64)") (class "Default")
      (node (ref "X1") (pin "64") (pinfunction "D13_64") (pintype "bidirectional"))
    )
    (net (code "130") (name "unconnected-(X1-D14-Pad66)") (class "Default")
      (node (ref "X1") (pin "66") (pinfunction "D14_66") (pintype "bidirectional"))
    )
    (net (code "131") (name "unconnected-(X1-D15-Pad68)") (class "Default")
      (node (ref "X1") (pin "68") (pinfunction "D15_68") (pintype "bidirectional"))
    )
    (net (code "132") (name "unconnected-(X1-NU0-Pad2)") (class "Default")
      (node (ref "X1") (pin "2") (pinfunction "NU0_2") (pintype "bidirectional"))
    )
    (net (code "133") (name "unconnected-(X1-NU1-Pad4)") (class "Default")
      (node (ref "X1") (pin "4") (pinfunction "NU1_4") (pintype "bidirectional"))
    )
    (net (code "134") (name "unconnected-(X1-NU2-Pad6)") (class "Default")
      (node (ref "X1") (pin "6") (pinfunction "NU2_6") (pintype "bidirectional"))
    )
    (net (code "135") (name "unconnected-(X1-NU3-Pad8)") (class "Default")
      (node (ref "X1") (pin "8") (pinfunction "NU3_8") (pintype "bidirectional"))
    )
    (net (code "136") (name "unconnected-(X1-NU4-Pad10)") (class "Default")
      (node (ref "X1") (pin "10") (pinfunction "NU4_10") (pintype "bidirectional"))
    )
    (net (code "137") (name "unconnected-(X1-NU5-Pad12)") (class "Default")
      (node (ref "X1") (pin "12") (pinfunction "NU5_12") (pintype "bidirectional"))
    )
    (net (code "138") (name "unconnected-(X1-NU6-Pad14)") (class "Default")
      (node (ref "X1") (pin "14") (pinfunction "NU6_14") (pintype "bidirectional"))
    )
    (net (code "139") (name "unconnected-(X1-NU7-Pad16)") (class "Default")
      (node (ref "X1") (pin "16") (pinfunction "NU7_16") (pintype "bidirectional"))
    )
    (net (code "140") (name "unconnected-(X1-PAGE-Pad40)") (class "Default")
      (node (ref "X1") (pin "40") (pinfunction "PAGE_40") (pintype "bidirectional"))
    )
    (net (code "141") (name "unconnected-(X1-RX-Pad71)") (class "Default")
      (node (ref "X1") (pin "71") (pinfunction "RX_71") (pintype "bidirectional"))
    )
    (net (code "142") (name "unconnected-(X1-RX2-Pad72)") (class "Default")
      (node (ref "X1") (pin "72") (pinfunction "RX2_72") (pintype "bidirectional"))
    )
    (net (code "143") (name "unconnected-(X1-TX-Pad69)") (class "Default")
      (node (ref "X1") (pin "69") (pinfunction "TX_69") (pintype "bidirectional"))
    )
    (net (code "144") (name "unconnected-(X1-TX2-Pad70)") (class "Default")
      (node (ref "X1") (pin "70") (pinfunction "TX2_70") (pintype "bidirectional"))
    )
    (net (code "145") (name "unconnected-(X1-USR3{slash}BAO-Pad77)") (class "Default")
      (node (ref "X1") (pin "77") (pinfunction "USR3/BAO_77") (pintype "bidirectional"))
    )
    (net (code "146") (name "unconnected-(X1-USR4{slash}IEO-Pad79)") (class "Default")
      (node (ref "X1") (pin "79") (pinfunction "USR4/IEO_79") (pintype "bidirectional"))
    )
    (net (code "147") (name "unconnected-(X1-USR5-Pad74)") (class "Default")
      (node (ref "X1") (pin "74") (pinfunction "USR5_74") (pintype "bidirectional"))
    )
    (net (code "148") (name "unconnected-(X1-USR6{slash}~{MEMDI}-Pad76)") (class "Default")
      (node (ref "X1") (pin "76") (pinfunction "USR6/~{MEMDI}_76") (pintype "bidirectional"))
    )
    (net (code "149") (name "unconnected-(X1-USR7{slash}BAI-Pad78)") (class "Default")
      (node (ref "X1") (pin "78") (pinfunction "USR7/BAI_78") (pintype "bidirectional"))
    )
    (net (code "150") (name "unconnected-(X1-USR8{slash}IEI-Pad80)") (class "Default")
      (node (ref "X1") (pin "80") (pinfunction "USR8/IEI_80") (pintype "bidirectional"))
    )
    (net (code "151") (name "unconnected-(X1-~{BUSACK}-Pad44)") (class "Default")
      (node (ref "X1") (pin "44") (pinfunction "~{BUSACK}_44") (pintype "bidirectional"))
    )
    (net (code "152") (name "unconnected-(X1-~{BUSREQ}-Pad48)") (class "Default")
      (node (ref "X1") (pin "48") (pinfunction "~{BUSREQ}_48") (pintype "bidirectional"))
    )
    (net (code "153") (name "unconnected-(X1-~{HALT}-Pad46)") (class "Default")
      (node (ref "X1") (pin "46") (pinfunction "~{HALT}_46") (pintype "bidirectional"))
    )
    (net (code "154") (name "unconnected-(X1-~{INT}-Pad43)") (class "Default")
      (node (ref "X1") (pin "43") (pinfunction "~{INT}_43") (pintype "bidirectional"))
    )
    (net (code "155") (name "unconnected-(X1-~{MREQ}-Pad45)") (class "Default")
      (node (ref "X1") (pin "45") (pinfunction "~{MREQ}_45") (pintype "bidirectional"))
    )
    (net (code "156") (name "unconnected-(X1-~{NMI}-Pad52)") (class "Default")
      (node (ref "X1") (pin "52") (pinfunction "~{NMI}_52") (pintype "bidirectional"))
    )
    (net (code "157") (name "unconnected-(X1-~{RFSH}-Pad38)") (class "Default")
      (node (ref "X1") (pin "38") (pinfunction "~{RFSH}_38") (pintype "bidirectional"))
    )
    (net (code "158") (name "unconnected-(X1-~{WAIT}-Pad50)") (class "Default")
      (node (ref "X1") (pin "50") (pinfunction "~{WAIT}_50") (pintype "bidirectional"))
    )
  )
)
